# ElekShemaRelais.net
KiCad netlist of a schematic drawn in Altium Designer
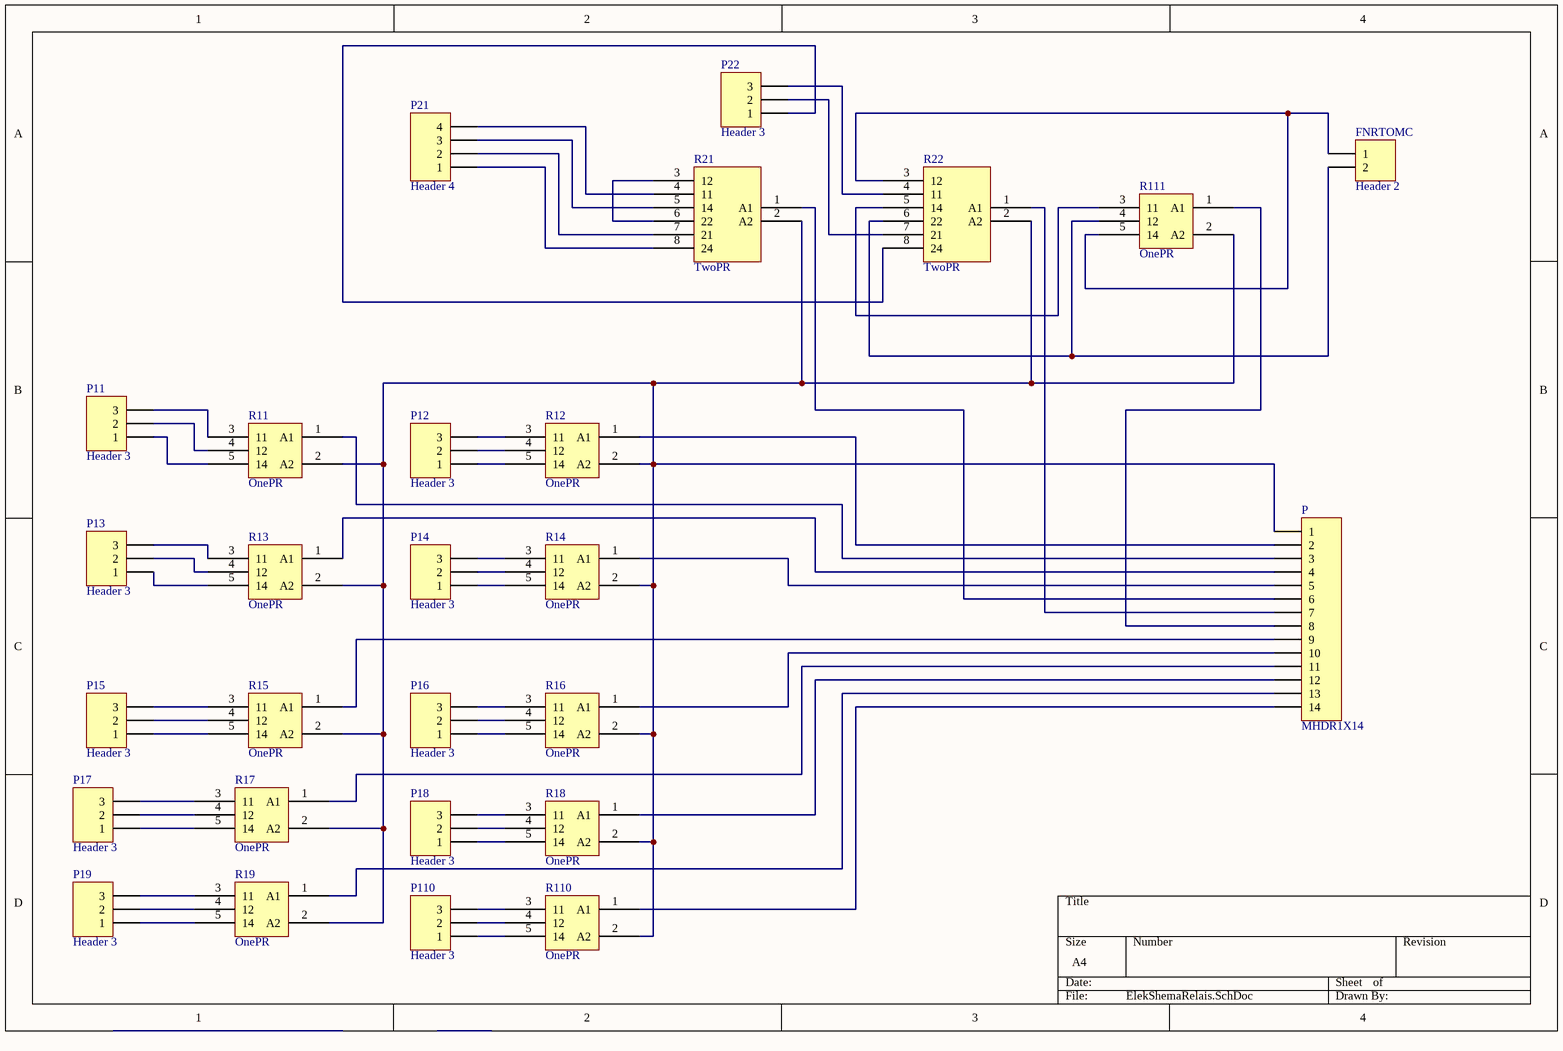
[diagram p0: ElekShemaRelais.SchDoc]

(export (version "E")
  (design (tool "Eeschema 10.0.6"))
  (components
    (comp (ref "FNRTOMC")
      (value "Header 2")
      (footprint "HDR1X2")
      (description "Header, 2-Pin")
      (fields (field (name "PUBLISHER") "Altium Limited"))
      (libsource (lib "Miscellaneous Connectors") (part "Header 2"))
    )
    (comp (ref "P")
      (value "MHDR1X14")
      (footprint "MHDR1X14")
      (description "Header, 14-Pin")
      (fields (field (name "PUBLISHER") "Altium Limited"))
      (libsource (lib "Miscellaneous Connectors") (part "MHDR1X14"))
    )
    (comp (ref "P11")
      (value "Header 3")
      (footprint "HDR1X3")
      (description "Header, 3-Pin")
      (fields (field (name "PUBLISHER") "Altium Limited"))
      (libsource (lib "Miscellaneous Connectors") (part "Header 3"))
    )
    (comp (ref "P12")
      (value "Header 3")
      (footprint "HDR1X3")
      (description "Header, 3-Pin")
      (fields (field (name "PUBLISHER") "Altium Limited"))
      (libsource (lib "Miscellaneous Connectors") (part "Header 3"))
    )
    (comp (ref "P13")
      (value "Header 3")
      (footprint "HDR1X3")
      (description "Header, 3-Pin")
      (fields (field (name "PUBLISHER") "Altium Limited"))
      (libsource (lib "Miscellaneous Connectors") (part "Header 3"))
    )
    (comp (ref "P14")
      (value "Header 3")
      (footprint "HDR1X3")
      (description "Header, 3-Pin")
      (fields (field (name "PUBLISHER") "Altium Limited"))
      (libsource (lib "Miscellaneous Connectors") (part "Header 3"))
    )
    (comp (ref "P15")
      (value "Header 3")
      (footprint "HDR1X3")
      (description "Header, 3-Pin")
      (fields (field (name "PUBLISHER") "Altium Limited"))
      (libsource (lib "Miscellaneous Connectors") (part "Header 3"))
    )
    (comp (ref "P16")
      (value "Header 3")
      (footprint "HDR1X3")
      (description "Header, 3-Pin")
      (fields (field (name "PUBLISHER") "Altium Limited"))
      (libsource (lib "Miscellaneous Connectors") (part "Header 3"))
    )
    (comp (ref "P17")
      (value "Header 3")
      (footprint "HDR1X3")
      (description "Header, 3-Pin")
      (fields (field (name "PUBLISHER") "Altium Limited"))
      (libsource (lib "Miscellaneous Connectors") (part "Header 3"))
    )
    (comp (ref "P18")
      (value "Header 3")
      (footprint "HDR1X3")
      (description "Header, 3-Pin")
      (fields (field (name "PUBLISHER") "Altium Limited"))
      (libsource (lib "Miscellaneous Connectors") (part "Header 3"))
    )
    (comp (ref "P19")
      (value "Header 3")
      (footprint "HDR1X3")
      (description "Header, 3-Pin")
      (fields (field (name "PUBLISHER") "Altium Limited"))
      (libsource (lib "Miscellaneous Connectors") (part "Header 3"))
    )
    (comp (ref "P21")
      (value "Header 4")
      (footprint "HDR1X4")
      (description "Header, 4-Pin")
      (fields (field (name "PUBLISHER") "Altium Limited"))
      (libsource (lib "Miscellaneous Connectors") (part "Header 4"))
    )
    (comp (ref "P22")
      (value "Header 3")
      (footprint "HDR1X3")
      (description "Header, 3-Pin")
      (fields (field (name "PUBLISHER") "Altium Limited"))
      (libsource (lib "Miscellaneous Connectors") (part "Header 3"))
    )
    (comp (ref "P110")
      (value "Header 3")
      (footprint "HDR1X3")
      (description "Header, 3-Pin")
      (fields (field (name "PUBLISHER") "Altium Limited"))
      (libsource (lib "Miscellaneous Connectors") (part "Header 3"))
    )
    (comp (ref "R11") (value "OnePR") (libsource (lib "Schlib1") (part "R1")))
    (comp (ref "R12") (value "OnePR") (libsource (lib "Schlib1") (part "R1")))
    (comp (ref "R13") (value "OnePR") (libsource (lib "Schlib1") (part "R1")))
    (comp (ref "R14") (value "OnePR") (libsource (lib "Schlib1") (part "R1")))
    (comp (ref "R15") (value "OnePR") (libsource (lib "Schlib1") (part "R1")))
    (comp (ref "R16") (value "OnePR") (libsource (lib "Schlib1") (part "R1")))
    (comp (ref "R17") (value "OnePR") (libsource (lib "Schlib1") (part "R1")))
    (comp (ref "R18") (value "OnePR") (libsource (lib "Schlib1") (part "R1")))
    (comp (ref "R19") (value "OnePR") (libsource (lib "Schlib1") (part "R1")))
    (comp (ref "R21") (value "TwoPR") (libsource (lib "Schlib1") (part "R2")))
    (comp (ref "R22") (value "TwoPR") (libsource (lib "Schlib1") (part "R2")))
    (comp (ref "R110") (value "OnePR") (libsource (lib "Schlib1") (part "R1")))
    (comp (ref "R111") (value "OnePR") (libsource (lib "Schlib1") (part "R1")))
  )
  (nets
    (net (code "1") (name "Net-(R11-11)") (class "Default")
      (node (ref "P11") (pin "3") (pinfunction "3_3") (pintype "passive"))
      (node (ref "R11") (pin "3") (pinfunction "11_3") (pintype "passive"))
    )
    (net (code "2") (name "Net-(R11-12)") (class "Default")
      (node (ref "P11") (pin "2") (pinfunction "2_2") (pintype "passive"))
      (node (ref "R11") (pin "4") (pinfunction "12_4") (pintype "passive"))
    )
    (net (code "3") (name "Net-(R11-14)") (class "Default")
      (node (ref "P11") (pin "1") (pinfunction "1_1") (pintype "passive"))
      (node (ref "R11") (pin "5") (pinfunction "14_5") (pintype "passive"))
    )
    (net (code "4") (name "Net-(R11-A1)") (class "Default")
      (node (ref "P") (pin "3") (pinfunction "3_3") (pintype "passive"))
      (node (ref "R11") (pin "1") (pinfunction "A1_1") (pintype "passive"))
    )
    (net (code "5") (name "Net-(R11-A2)") (class "Default")
      (node (ref "P") (pin "1") (pinfunction "1_1") (pintype "passive"))
      (node (ref "R11") (pin "2") (pinfunction "A2_2") (pintype "passive"))
      (node (ref "R110") (pin "2") (pinfunction "A2_2") (pintype "passive"))
      (node (ref "R111") (pin "2") (pinfunction "A2_2") (pintype "passive"))
      (node (ref "R12") (pin "2") (pinfunction "A2_2") (pintype "passive"))
      (node (ref "R13") (pin "2") (pinfunction "A2_2") (pintype "passive"))
      (node (ref "R14") (pin "2") (pinfunction "A2_2") (pintype "passive"))
      (node (ref "R15") (pin "2") (pinfunction "A2_2") (pintype "passive"))
      (node (ref "R16") (pin "2") (pinfunction "A2_2") (pintype "passive"))
      (node (ref "R17") (pin "2") (pinfunction "A2_2") (pintype "passive"))
      (node (ref "R18") (pin "2") (pinfunction "A2_2") (pintype "passive"))
      (node (ref "R19") (pin "2") (pinfunction "A2_2") (pintype "passive"))
      (node (ref "R21") (pin "2") (pinfunction "A2_2") (pintype "passive"))
      (node (ref "R22") (pin "2") (pinfunction "A2_2") (pintype "passive"))
    )
    (net (code "6") (name "Net-(R12-11)") (class "Default")
      (node (ref "P12") (pin "3") (pinfunction "3_3") (pintype "passive"))
      (node (ref "R12") (pin "3") (pinfunction "11_3") (pintype "passive"))
    )
    (net (code "7") (name "Net-(R12-12)") (class "Default")
      (node (ref "P12") (pin "2") (pinfunction "2_2") (pintype "passive"))
      (node (ref "R12") (pin "4") (pinfunction "12_4") (pintype "passive"))
    )
    (net (code "8") (name "Net-(R12-14)") (class "Default")
      (node (ref "P12") (pin "1") (pinfunction "1_1") (pintype "passive"))
      (node (ref "R12") (pin "5") (pinfunction "14_5") (pintype "passive"))
    )
    (net (code "9") (name "Net-(R12-A1)") (class "Default")
      (node (ref "P") (pin "2") (pinfunction "2_2") (pintype "passive"))
      (node (ref "R12") (pin "1") (pinfunction "A1_1") (pintype "passive"))
    )
    (net (code "10") (name "Net-(R13-11)") (class "Default")
      (node (ref "P13") (pin "3") (pinfunction "3_3") (pintype "passive"))
      (node (ref "R13") (pin "3") (pinfunction "11_3") (pintype "passive"))
    )
    (net (code "11") (name "Net-(R13-12)") (class "Default")
      (node (ref "P13") (pin "2") (pinfunction "2_2") (pintype "passive"))
      (node (ref "R13") (pin "4") (pinfunction "12_4") (pintype "passive"))
    )
    (net (code "12") (name "Net-(R13-14)") (class "Default")
      (node (ref "P13") (pin "1") (pinfunction "1_1") (pintype "passive"))
      (node (ref "R13") (pin "5") (pinfunction "14_5") (pintype "passive"))
    )
    (net (code "13") (name "Net-(R13-A1)") (class "Default")
      (node (ref "P") (pin "4") (pinfunction "4_4") (pintype "passive"))
      (node (ref "R13") (pin "1") (pinfunction "A1_1") (pintype "passive"))
    )
    (net (code "14") (name "Net-(R14-11)") (class "Default")
      (node (ref "P14") (pin "3") (pinfunction "3_3") (pintype "passive"))
      (node (ref "R14") (pin "3") (pinfunction "11_3") (pintype "passive"))
    )
    (net (code "15") (name "Net-(R14-12)") (class "Default")
      (node (ref "P14") (pin "2") (pinfunction "2_2") (pintype "passive"))
      (node (ref "R14") (pin "4") (pinfunction "12_4") (pintype "passive"))
    )
    (net (code "16") (name "Net-(R14-14)") (class "Default")
      (node (ref "P14") (pin "1") (pinfunction "1_1") (pintype "passive"))
      (node (ref "R14") (pin "5") (pinfunction "14_5") (pintype "passive"))
    )
    (net (code "17") (name "Net-(R14-A1)") (class "Default")
      (node (ref "P") (pin "5") (pinfunction "5_5") (pintype "passive"))
      (node (ref "R14") (pin "1") (pinfunction "A1_1") (pintype "passive"))
    )
    (net (code "18") (name "Net-(R15-11)") (class "Default")
      (node (ref "P15") (pin "3") (pinfunction "3_3") (pintype "passive"))
      (node (ref "R15") (pin "3") (pinfunction "11_3") (pintype "passive"))
    )
    (net (code "19") (name "Net-(R15-12)") (class "Default")
      (node (ref "P15") (pin "2") (pinfunction "2_2") (pintype "passive"))
      (node (ref "R15") (pin "4") (pinfunction "12_4") (pintype "passive"))
    )
    (net (code "20") (name "Net-(R15-14)") (class "Default")
      (node (ref "P15") (pin "1") (pinfunction "1_1") (pintype "passive"))
      (node (ref "R15") (pin "5") (pinfunction "14_5") (pintype "passive"))
    )
    (net (code "21") (name "Net-(R15-A1)") (class "Default")
      (node (ref "P") (pin "9") (pinfunction "9_9") (pintype "passive"))
      (node (ref "R15") (pin "1") (pinfunction "A1_1") (pintype "passive"))
    )
    (net (code "22") (name "Net-(R16-11)") (class "Default")
      (node (ref "P16") (pin "3") (pinfunction "3_3") (pintype "passive"))
      (node (ref "R16") (pin "3") (pinfunction "11_3") (pintype "passive"))
    )
    (net (code "23") (name "Net-(R16-12)") (class "Default")
      (node (ref "P16") (pin "2") (pinfunction "2_2") (pintype "passive"))
      (node (ref "R16") (pin "4") (pinfunction "12_4") (pintype "passive"))
    )
    (net (code "24") (name "Net-(R16-14)") (class "Default")
      (node (ref "P16") (pin "1") (pinfunction "1_1") (pintype "passive"))
      (node (ref "R16") (pin "5") (pinfunction "14_5") (pintype "passive"))
    )
    (net (code "25") (name "Net-(R16-A1)") (class "Default")
      (node (ref "P") (pin "10") (pinfunction "10_10") (pintype "passive"))
      (node (ref "R16") (pin "1") (pinfunction "A1_1") (pintype "passive"))
    )
    (net (code "26") (name "Net-(R17-11)") (class "Default")
      (node (ref "P17") (pin "3") (pinfunction "3_3") (pintype "passive"))
      (node (ref "R17") (pin "3") (pinfunction "11_3") (pintype "passive"))
    )
    (net (code "27") (name "Net-(R17-12)") (class "Default")
      (node (ref "P17") (pin "2") (pinfunction "2_2") (pintype "passive"))
      (node (ref "R17") (pin "4") (pinfunction "12_4") (pintype "passive"))
    )
    (net (code "28") (name "Net-(R17-14)") (class "Default")
      (node (ref "P17") (pin "1") (pinfunction "1_1") (pintype "passive"))
      (node (ref "R17") (pin "5") (pinfunction "14_5") (pintype "passive"))
    )
    (net (code "29") (name "Net-(R17-A1)") (class "Default")
      (node (ref "P") (pin "11") (pinfunction "11_11") (pintype "passive"))
      (node (ref "R17") (pin "1") (pinfunction "A1_1") (pintype "passive"))
    )
    (net (code "30") (name "Net-(R18-11)") (class "Default")
      (node (ref "P18") (pin "3") (pinfunction "3_3") (pintype "passive"))
      (node (ref "R18") (pin "3") (pinfunction "11_3") (pintype "passive"))
    )
    (net (code "31") (name "Net-(R18-12)") (class "Default")
      (node (ref "P18") (pin "2") (pinfunction "2_2") (pintype "passive"))
      (node (ref "R18") (pin "4") (pinfunction "12_4") (pintype "passive"))
    )
    (net (code "32") (name "Net-(R18-14)") (class "Default")
      (node (ref "P18") (pin "1") (pinfunction "1_1") (pintype "passive"))
      (node (ref "R18") (pin "5") (pinfunction "14_5") (pintype "passive"))
    )
    (net (code "33") (name "Net-(R18-A1)") (class "Default")
      (node (ref "P") (pin "12") (pinfunction "12_12") (pintype "passive"))
      (node (ref "R18") (pin "1") (pinfunction "A1_1") (pintype "passive"))
    )
    (net (code "34") (name "Net-(R19-11)") (class "Default")
      (node (ref "P19") (pin "3") (pinfunction "3_3") (pintype "passive"))
      (node (ref "R19") (pin "3") (pinfunction "11_3") (pintype "passive"))
    )
    (net (code "35") (name "Net-(R19-12)") (class "Default")
      (node (ref "P19") (pin "2") (pinfunction "2_2") (pintype "passive"))
      (node (ref "R19") (pin "4") (pinfunction "12_4") (pintype "passive"))
    )
    (net (code "36") (name "Net-(R19-14)") (class "Default")
      (node (ref "P19") (pin "1") (pinfunction "1_1") (pintype "passive"))
      (node (ref "R19") (pin "5") (pinfunction "14_5") (pintype "passive"))
    )
    (net (code "37") (name "Net-(R19-A1)") (class "Default")
      (node (ref "P") (pin "13") (pinfunction "13_13") (pintype "passive"))
      (node (ref "R19") (pin "1") (pinfunction "A1_1") (pintype "passive"))
    )
    (net (code "38") (name "Net-(R21-11)") (class "Default")
      (node (ref "P21") (pin "4") (pinfunction "4_4") (pintype "passive"))
      (node (ref "R21") (pin "4") (pinfunction "11_4") (pintype "passive"))
    )
    (net (code "39") (name "Net-(R21-12)") (class "Default")
      (node (ref "R21") (pin "3") (pinfunction "12_3") (pintype "passive"))
      (node (ref "R21") (pin "6") (pinfunction "22_6") (pintype "passive"))
    )
    (net (code "40") (name "Net-(R21-14)") (class "Default")
      (node (ref "P21") (pin "3") (pinfunction "3_3") (pintype "passive"))
      (node (ref "R21") (pin "5") (pinfunction "14_5") (pintype "passive"))
    )
    (net (code "41") (name "Net-(R21-21)") (class "Default")
      (node (ref "P21") (pin "2") (pinfunction "2_2") (pintype "passive"))
      (node (ref "R21") (pin "7") (pinfunction "21_7") (pintype "passive"))
    )
    (net (code "42") (name "Net-(R21-24)") (class "Default")
      (node (ref "P21") (pin "1") (pinfunction "1_1") (pintype "passive"))
      (node (ref "R21") (pin "8") (pinfunction "24_8") (pintype "passive"))
    )
    (net (code "43") (name "Net-(R21-A1)") (class "Default")
      (node (ref "P") (pin "6") (pinfunction "6_6") (pintype "passive"))
      (node (ref "R21") (pin "1") (pinfunction "A1_1") (pintype "passive"))
    )
    (net (code "44") (name "Net-(R22-11)") (class "Default")
      (node (ref "P22") (pin "3") (pinfunction "3_3") (pintype "passive"))
      (node (ref "R22") (pin "4") (pinfunction "11_4") (pintype "passive"))
    )
    (net (code "45") (name "Net-(R22-21)") (class "Default")
      (node (ref "P22") (pin "2") (pinfunction "2_2") (pintype "passive"))
      (node (ref "R22") (pin "7") (pinfunction "21_7") (pintype "passive"))
    )
    (net (code "46") (name "Net-(R22-24)") (class "Default")
      (node (ref "P22") (pin "1") (pinfunction "1_1") (pintype "passive"))
      (node (ref "R22") (pin "8") (pinfunction "24_8") (pintype "passive"))
    )
    (net (code "47") (name "Net-(R22-A1)") (class "Default")
      (node (ref "P") (pin "7") (pinfunction "7_7") (pintype "passive"))
      (node (ref "R22") (pin "1") (pinfunction "A1_1") (pintype "passive"))
    )
    (net (code "48") (name "Net-(R110-11)") (class "Default")
      (node (ref "P110") (pin "3") (pinfunction "3_3") (pintype "passive"))
      (node (ref "R110") (pin "3") (pinfunction "11_3") (pintype "passive"))
    )
    (net (code "49") (name "Net-(R110-12)") (class "Default")
      (node (ref "P110") (pin "2") (pinfunction "2_2") (pintype "passive"))
      (node (ref "R110") (pin "4") (pinfunction "12_4") (pintype "passive"))
    )
    (net (code "50") (name "Net-(R110-14)") (class "Default")
      (node (ref "P110") (pin "1") (pinfunction "1_1") (pintype "passive"))
      (node (ref "R110") (pin "5") (pinfunction "14_5") (pintype "passive"))
    )
    (net (code "51") (name "Net-(R110-A1)") (class "Default")
      (node (ref "P") (pin "14") (pinfunction "14_14") (pintype "passive"))
      (node (ref "R110") (pin "1") (pinfunction "A1_1") (pintype "passive"))
    )
    (net (code "52") (name "Net-(R111-11)") (class "Default")
      (node (ref "R111") (pin "3") (pinfunction "11_3") (pintype "passive"))
      (node (ref "R22") (pin "5") (pinfunction "14_5") (pintype "passive"))
    )
    (net (code "53") (name "Net-(R111-12)") (class "Default")
      (node (ref "FNRTOMC") (pin "2") (pinfunction "2_2") (pintype "passive"))
      (node (ref "R111") (pin "4") (pinfunction "12_4") (pintype "passive"))
      (node (ref "R22") (pin "6") (pinfunction "22_6") (pintype "passive"))
    )
    (net (code "54") (name "Net-(R111-14)") (class "Default")
      (node (ref "FNRTOMC") (pin "1") (pinfunction "1_1") (pintype "passive"))
      (node (ref "R111") (pin "5") (pinfunction "14_5") (pintype "passive"))
      (node (ref "R22") (pin "3") (pinfunction "12_3") (pintype "passive"))
    )
    (net (code "55") (name "Net-(R111-A1)") (class "Default")
      (node (ref "P") (pin "8") (pinfunction "8_8") (pintype "passive"))
      (node (ref "R111") (pin "1") (pinfunction "A1_1") (pintype "passive"))
    )
  )
)
